# IMU2_BREAKOUT.net
KiCad netlist of a schematic drawn in EAGLE
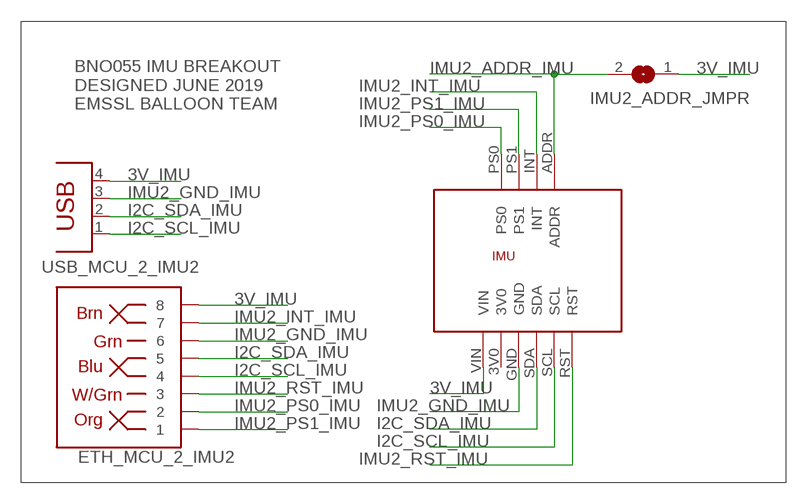
[diagram p0: schematic, sheet 1]

(export (version "E")
  (design (tool "Eeschema 10.0.6"))
  (components
    (comp (ref "ETH_MCU_2_IMU2")
      (value "RJ45")
      (footprint "eagle-import:RJ45-8")
      (libsource (lib "eagle-import") (part "RJ45-8"))
    )
    (comp (ref "IMU2")
      (value "BNO055")
      (footprint "eagle-import:BNO055")
      (libsource (lib "eagle-import") (part "BNO055"))
    )
    (comp (ref "IMU2_ADDR_JMPR")
      (value "SJ")
      (footprint "eagle-import:SJ")
      (libsource (lib "eagle-import") (part "SJ"))
    )
    (comp (ref "USB_MCU_2_IMU2")
      (value "PN87520")
      (footprint "eagle-import:PN87520")
      (libsource (lib "eagle-import") (part "PN87520"))
    )
  )
  (nets
    (net (code "1") (name "/3V_IMU") (class "Default")
      (node (ref "ETH_MCU_2_IMU2") (pin "8") (pinfunction "8_8") (pintype "bidirectional"))
      (node (ref "IMU2") (pin "VIN") (pinfunction "VIN_VIN") (pintype "bidirectional"))
      (node (ref "IMU2_ADDR_JMPR") (pin "1") (pinfunction "1_1") (pintype "passive"))
      (node (ref "USB_MCU_2_IMU2") (pin "4") (pinfunction "4_4") (pintype "passive"))
    )
    (net (code "2") (name "/I2C_SCL_IMU") (class "Default")
      (node (ref "ETH_MCU_2_IMU2") (pin "4") (pinfunction "4_4") (pintype "bidirectional"))
      (node (ref "IMU2") (pin "SCL") (pinfunction "SCL_SCL") (pintype "bidirectional"))
      (node (ref "USB_MCU_2_IMU2") (pin "1") (pinfunction "1_1") (pintype "passive"))
    )
    (net (code "3") (name "/I2C_SDA_IMU") (class "Default")
      (node (ref "ETH_MCU_2_IMU2") (pin "5") (pinfunction "5_5") (pintype "bidirectional"))
      (node (ref "IMU2") (pin "SDA") (pinfunction "SDA_SDA") (pintype "bidirectional"))
      (node (ref "USB_MCU_2_IMU2") (pin "2") (pinfunction "2_2") (pintype "passive"))
    )
    (net (code "4") (name "/IMU2_ADDR_IMU") (class "Default")
      (node (ref "IMU2") (pin "ADDR") (pinfunction "ADDR_ADDR") (pintype "bidirectional"))
      (node (ref "IMU2_ADDR_JMPR") (pin "2") (pinfunction "2_2") (pintype "passive"))
    )
    (net (code "5") (name "/IMU2_GND_IMU") (class "Default")
      (node (ref "ETH_MCU_2_IMU2") (pin "6") (pinfunction "6_6") (pintype "bidirectional"))
      (node (ref "IMU2") (pin "GND") (pinfunction "GND_GND") (pintype "bidirectional"))
      (node (ref "USB_MCU_2_IMU2") (pin "3") (pinfunction "3_3") (pintype "passive"))
    )
    (net (code "6") (name "/IMU2_INT_IMU") (class "Default")
      (node (ref "ETH_MCU_2_IMU2") (pin "7") (pinfunction "7_7") (pintype "bidirectional"))
      (node (ref "IMU2") (pin "INT") (pinfunction "INT_INT") (pintype "bidirectional"))
    )
    (net (code "7") (name "/IMU2_PS0_IMU") (class "Default")
      (node (ref "ETH_MCU_2_IMU2") (pin "2") (pinfunction "2_2") (pintype "bidirectional"))
      (node (ref "IMU2") (pin "PS0") (pinfunction "PS0_PS0") (pintype "bidirectional"))
    )
    (net (code "8") (name "/IMU2_PS1_IMU") (class "Default")
      (node (ref "ETH_MCU_2_IMU2") (pin "1") (pinfunction "1_1") (pintype "bidirectional"))
      (node (ref "IMU2") (pin "PS1") (pinfunction "PS1_PS1") (pintype "bidirectional"))
    )
    (net (code "9") (name "/IMU2_RST_IMU") (class "Default")
      (node (ref "ETH_MCU_2_IMU2") (pin "3") (pinfunction "3_3") (pintype "bidirectional"))
      (node (ref "IMU2") (pin "RST") (pinfunction "RST_RST") (pintype "bidirectional"))
    )
    (net (code "10") (name "unconnected-(IMU2-Pad3V0)") (class "Default")
      (node (ref "IMU2") (pin "3V0") (pinfunction "3V0_3V0") (pintype "bidirectional"))
    )
  )
)
